# Server_Buttons.net
KiCad netlist of a schematic drawn in Altium Designer
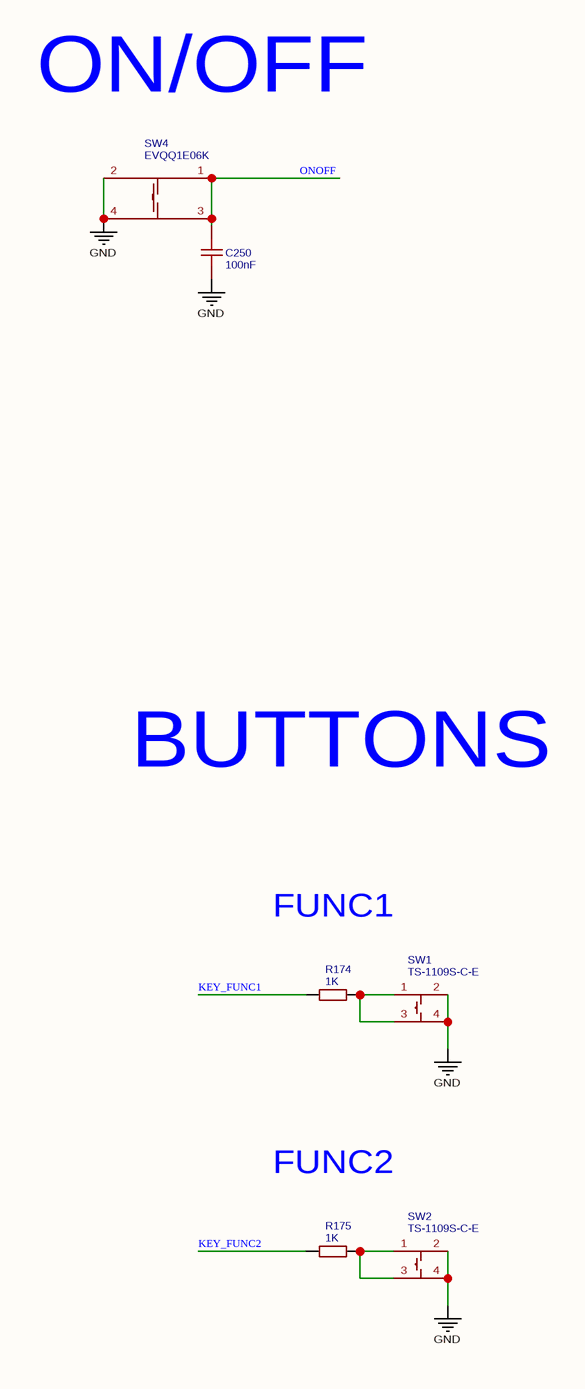
[diagram p0: Server Buttons.schdoc, left]
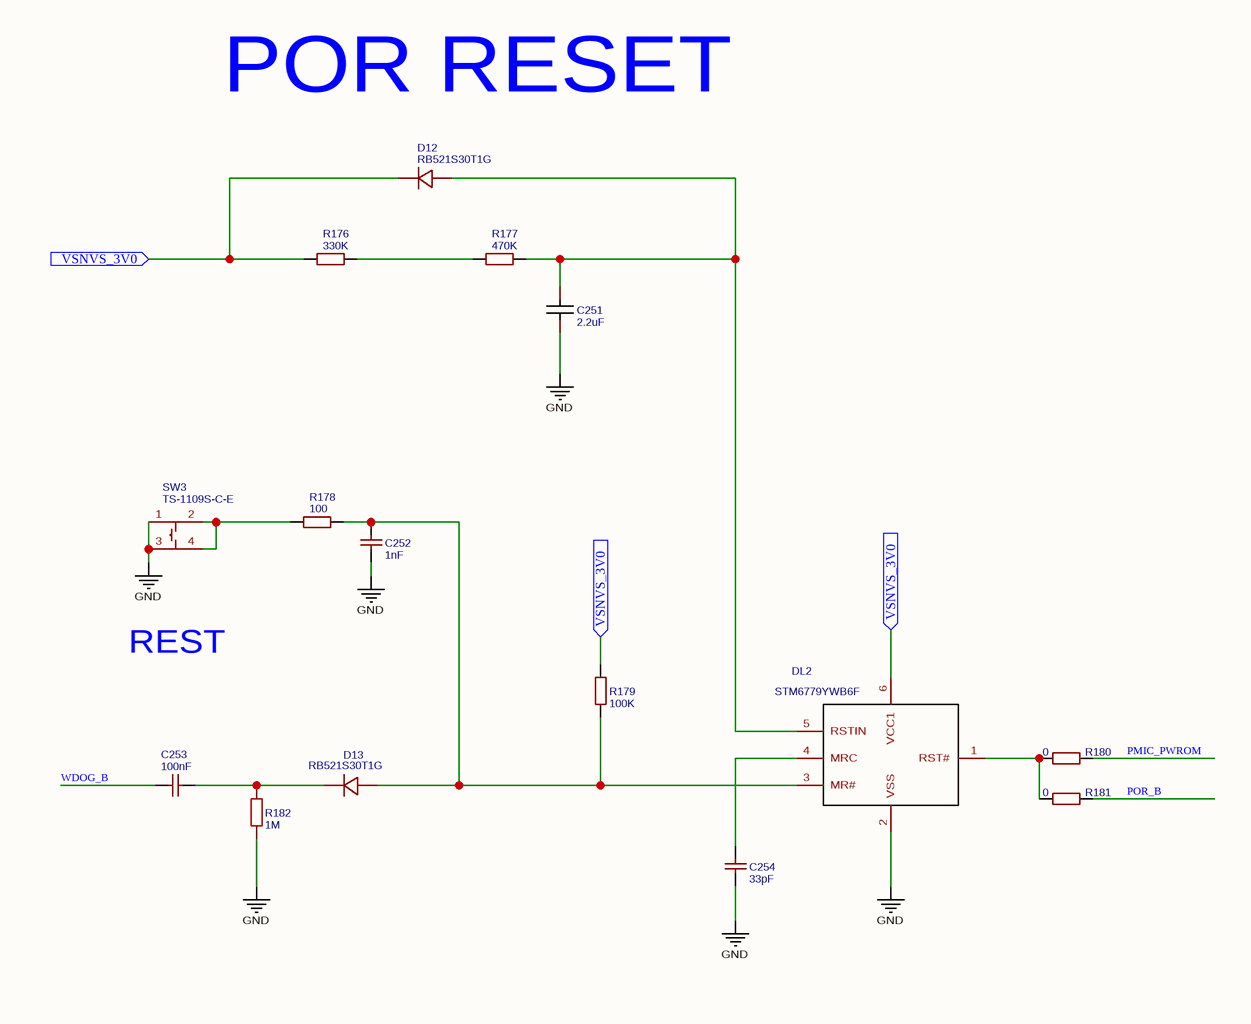
[diagram p1: Server Buttons.schdoc, right]

(export (version "E")
  (design (tool "Eeschema 10.0.6"))
  (components
    (comp (ref "C250")
      (value "100nF")
      (fields
        (field (name "BOM_MANUFACTURER PART") "CC0603KRX7R9BB104")
        (field (name "BOM_SUPPLIER PART") "C14663")
      )
      (libsource (lib "altium-import") (part "root_1_100nF_"))
    )
    (comp (ref "C251")
      (value "2.2uF")
      (fields
        (field (name "BOM_MANUFACTURER PART") "CL05A225MQ5NSNC")
        (field (name "BOM_SUPPLIER PART") "C12530")
      )
      (libsource (lib "altium-import") (part "root_1_2.2uF_"))
    )
    (comp (ref "C252")
      (value "1nF")
      (fields
        (field (name "BOM_MANUFACTURER PART") "CL21B102KBCNNNC")
        (field (name "BOM_SUPPLIER PART") "C46653")
      )
      (libsource (lib "altium-import") (part "root_1_1nF_"))
    )
    (comp (ref "C253")
      (value "100nF")
      (fields
        (field (name "BOM_MANUFACTURER PART") "CL05B104KO5NNNC")
        (field (name "BOM_SUPPLIER PART") "C1525")
      )
      (libsource (lib "altium-import") (part "root_2_100nF_"))
    )
    (comp (ref "C254")
      (value "33pF")
      (fields
        (field (name "BOM_MANUFACTURER PART") "0402CG330J500NT")
        (field (name "BOM_SUPPLIER PART") "C1562")
      )
      (libsource (lib "altium-import") (part "root_1_33pF_"))
    )
    (comp (ref "D12")
      (value "RB521S30T1G")
      (fields (field (name "BOM_SUPPLIER PART") "C145179") (field (name "CONTRIBUTOR") "LCSC"))
      (libsource (lib "altium-import") (part "root_0_RB521S30T1G_"))
    )
    (comp (ref "D13")
      (value "RB521S30T1G")
      (fields (field (name "BOM_SUPPLIER PART") "C145179") (field (name "CONTRIBUTOR") "LCSC"))
      (libsource (lib "altium-import") (part "root_0_RB521S30T1G_"))
    )
    (comp (ref "DL2")
      (value "STM6779YWB6F")
      (fields (field (name "CONTRIBUTOR") "Ke'Ondrae_Mell"))
      (libsource (lib "altium-import") (part "root_0_STM6779YWB6F_"))
    )
    (comp (ref "R174")
      (value "1K")
      (fields
        (field (name "BOM_MANUFACTURER PART") "0402WGF1001TCE")
        (field (name "BOM_SUPPLIER PART") "C11702")
      )
      (libsource (lib "altium-import") (part "root_0_1K_"))
    )
    (comp (ref "R175")
      (value "1K")
      (fields
        (field (name "BOM_MANUFACTURER PART") "0402WGF1001TCE")
        (field (name "BOM_SUPPLIER PART") "C11702")
      )
      (libsource (lib "altium-import") (part "root_0_1K_"))
    )
    (comp (ref "R176")
      (value "330K")
      (fields
        (field (name "BOM_MANUFACTURER PART") "0402WGF3303TCE")
        (field (name "BOM_SUPPLIER PART") "C25778")
      )
      (libsource (lib "altium-import") (part "root_0_330K_"))
    )
    (comp (ref "R177")
      (value "470K")
      (fields
        (field (name "BOM_MANUFACTURER PART") "0402WGF4703TCE")
        (field (name "BOM_SUPPLIER PART") "C25790")
      )
      (libsource (lib "altium-import") (part "root_0_470K_"))
    )
    (comp (ref "R178")
      (value "100")
      (fields
        (field (name "BOM_MANUFACTURER PART") "0402WGF1000TCE")
        (field (name "BOM_SUPPLIER PART") "C25076")
      )
      (libsource (lib "altium-import") (part "root_0_100_"))
    )
    (comp (ref "R179")
      (value "100K")
      (fields
        (field (name "BOM_MANUFACTURER PART") "0402WGF1003TCE")
        (field (name "BOM_SUPPLIER PART") "C25741")
      )
      (libsource (lib "altium-import") (part "root_1_100K_"))
    )
    (comp (ref "R180")
      (value "0")
      (fields
        (field (name "BOM_MANUFACTURER PART") "RK73Z1ETTP")
        (field (name "BOM_SUPPLIER PART") "C131359")
      )
      (libsource (lib "altium-import") (part "root_0_0_"))
    )
    (comp (ref "R181")
      (value "0")
      (fields
        (field (name "BOM_MANUFACTURER PART") "RK73Z1ETTP")
        (field (name "BOM_SUPPLIER PART") "C131359")
      )
      (libsource (lib "altium-import") (part "root_0_0_"))
    )
    (comp (ref "R182")
      (value "1M")
      (fields
        (field (name "BOM_SUPPLIER PART") "C269705")
        (field (name "BOM_MANUFACTURER PART") "RMC06031M1%N")
        (field (name "CONTRIBUTOR") "LCSC")
      )
      (libsource (lib "altium-import") (part "root_1_1M_"))
    )
    (comp (ref "SW1")
      (value "TS-1109S-C-E")
      (fields (field (name "BOM_SUPPLIER PART") "C561507") (field (name "CONTRIBUTOR") "LCSC"))
      (libsource (lib "altium-import") (part "root_0_TS-1109S-C-E_"))
    )
    (comp (ref "SW2")
      (value "TS-1109S-C-E")
      (fields (field (name "BOM_SUPPLIER PART") "C561507") (field (name "CONTRIBUTOR") "LCSC"))
      (libsource (lib "altium-import") (part "root_0_TS-1109S-C-E_"))
    )
    (comp (ref "SW3")
      (value "TS-1109S-C-E")
      (fields (field (name "BOM_SUPPLIER PART") "C561507") (field (name "CONTRIBUTOR") "LCSC"))
      (libsource (lib "altium-import") (part "root_0_TS-1109S-C-E_"))
    )
    (comp (ref "SW4")
      (value "EVQQ1E06K")
      (fields (field (name "BOM_SUPPLIER PART") "C79177") (field (name "CONTRIBUTOR") "LCSC"))
      (libsource (lib "altium-import") (part "root_0_EVQQ1E06K_"))
    )
  )
  (nets
    (net (code "1") (name "/KEY_FUNC1") (class "Default")
      (node (ref "R174") (pin "1") (pinfunction "1_1") (pintype "passive"))
    )
    (net (code "2") (name "/KEY_FUNC2") (class "Default")
      (node (ref "R175") (pin "1") (pinfunction "1_1") (pintype "passive"))
    )
    (net (code "3") (name "/ONOFF") (class "Default")
      (node (ref "C250") (pin "2") (pinfunction "2_2") (pintype "passive"))
      (node (ref "SW4") (pin "1") (pinfunction "1_1") (pintype "passive"))
      (node (ref "SW4") (pin "3") (pinfunction "3_3") (pintype "passive"))
    )
    (net (code "4") (name "/PMIC_PWROM") (class "Default")
      (node (ref "R180") (pin "2") (pinfunction "2_2") (pintype "passive"))
    )
    (net (code "5") (name "/POR_B") (class "Default")
      (node (ref "R181") (pin "2") (pinfunction "2_2") (pintype "passive"))
    )
    (net (code "6") (name "/VSNVS_3V0") (class "Default")
      (node (ref "D12") (pin "1") (pinfunction "C_1") (pintype "passive"))
      (node (ref "DL2") (pin "6") (pinfunction "VCC1_6") (pintype "passive"))
      (node (ref "R176") (pin "1") (pinfunction "1_1") (pintype "passive"))
      (node (ref "R179") (pin "2") (pinfunction "2_2") (pintype "passive"))
    )
    (net (code "7") (name "/WDOG_B") (class "Default")
      (node (ref "C253") (pin "2") (pinfunction "2_2") (pintype "passive"))
    )
    (net (code "8") (name "GND") (class "Default")
      (node (ref "C250") (pin "1") (pinfunction "1_1") (pintype "passive"))
      (node (ref "C251") (pin "1") (pinfunction "1_1") (pintype "passive"))
      (node (ref "C252") (pin "1") (pinfunction "1_1") (pintype "passive"))
      (node (ref "C254") (pin "1") (pinfunction "1_1") (pintype "passive"))
      (node (ref "DL2") (pin "2") (pinfunction "VSS_2") (pintype "passive"))
      (node (ref "R182") (pin "1") (pinfunction "1_1") (pintype "passive"))
      (node (ref "SW1") (pin "2") (pinfunction "2_2") (pintype "passive"))
      (node (ref "SW1") (pin "4") (pinfunction "4_4") (pintype "passive"))
      (node (ref "SW2") (pin "2") (pinfunction "2_2") (pintype "passive"))
      (node (ref "SW2") (pin "4") (pinfunction "4_4") (pintype "passive"))
      (node (ref "SW3") (pin "1") (pinfunction "1_1") (pintype "passive"))
      (node (ref "SW3") (pin "3") (pinfunction "3_3") (pintype "passive"))
      (node (ref "SW4") (pin "2") (pinfunction "2_2") (pintype "passive"))
      (node (ref "SW4") (pin "4") (pinfunction "4_4") (pintype "passive"))
    )
    (net (code "9") (name "Net-(D12-A)") (class "Default")
      (node (ref "C251") (pin "2") (pinfunction "2_2") (pintype "passive"))
      (node (ref "D12") (pin "2") (pinfunction "A_2") (pintype "passive"))
      (node (ref "DL2") (pin "5") (pinfunction "RSTIN_5") (pintype "passive"))
      (node (ref "R177") (pin "2") (pinfunction "2_2") (pintype "passive"))
    )
    (net (code "10") (name "Net-(D13-A)") (class "Default")
      (node (ref "C252") (pin "2") (pinfunction "2_2") (pintype "passive"))
      (node (ref "D13") (pin "2") (pinfunction "A_2") (pintype "passive"))
      (node (ref "DL2") (pin "3") (pinfunction "MR#_3") (pintype "passive"))
      (node (ref "R178") (pin "2") (pinfunction "2_2") (pintype "passive"))
      (node (ref "R179") (pin "1") (pinfunction "1_1") (pintype "passive"))
    )
    (net (code "11") (name "Net-(D13-C)") (class "Default")
      (node (ref "C253") (pin "1") (pinfunction "1_1") (pintype "passive"))
      (node (ref "D13") (pin "1") (pinfunction "C_1") (pintype "passive"))
      (node (ref "R182") (pin "2") (pinfunction "2_2") (pintype "passive"))
    )
    (net (code "12") (name "Net-(DL2-MRC)") (class "Default")
      (node (ref "C254") (pin "2") (pinfunction "2_2") (pintype "passive"))
      (node (ref "DL2") (pin "4") (pinfunction "MRC_4") (pintype "passive"))
    )
    (net (code "13") (name "Net-(DL2-RST#)") (class "Default")
      (node (ref "DL2") (pin "1") (pinfunction "RST#_1") (pintype "passive"))
      (node (ref "R180") (pin "1") (pinfunction "1_1") (pintype "passive"))
      (node (ref "R181") (pin "1") (pinfunction "1_1") (pintype "passive"))
    )
    (net (code "14") (name "Net-(R174-Pad2)") (class "Default")
      (node (ref "R174") (pin "2") (pinfunction "2_2") (pintype "passive"))
      (node (ref "SW1") (pin "1") (pinfunction "1_1") (pintype "passive"))
      (node (ref "SW1") (pin "3") (pinfunction "3_3") (pintype "passive"))
    )
    (net (code "15") (name "Net-(R175-Pad2)") (class "Default")
      (node (ref "R175") (pin "2") (pinfunction "2_2") (pintype "passive"))
      (node (ref "SW2") (pin "1") (pinfunction "1_1") (pintype "passive"))
      (node (ref "SW2") (pin "3") (pinfunction "3_3") (pintype "passive"))
    )
    (net (code "16") (name "Net-(R176-Pad2)") (class "Default")
      (node (ref "R176") (pin "2") (pinfunction "2_2") (pintype "passive"))
      (node (ref "R177") (pin "1") (pinfunction "1_1") (pintype "passive"))
    )
    (net (code "17") (name "Net-(R178-Pad1)") (class "Default")
      (node (ref "R178") (pin "1") (pinfunction "1_1") (pintype "passive"))
      (node (ref "SW3") (pin "2") (pinfunction "2_2") (pintype "passive"))
      (node (ref "SW3") (pin "4") (pinfunction "4_4") (pintype "passive"))
    )
  )
)
